# fanRegulator2.net
KiCad netlist of a schematic drawn in EAGLE
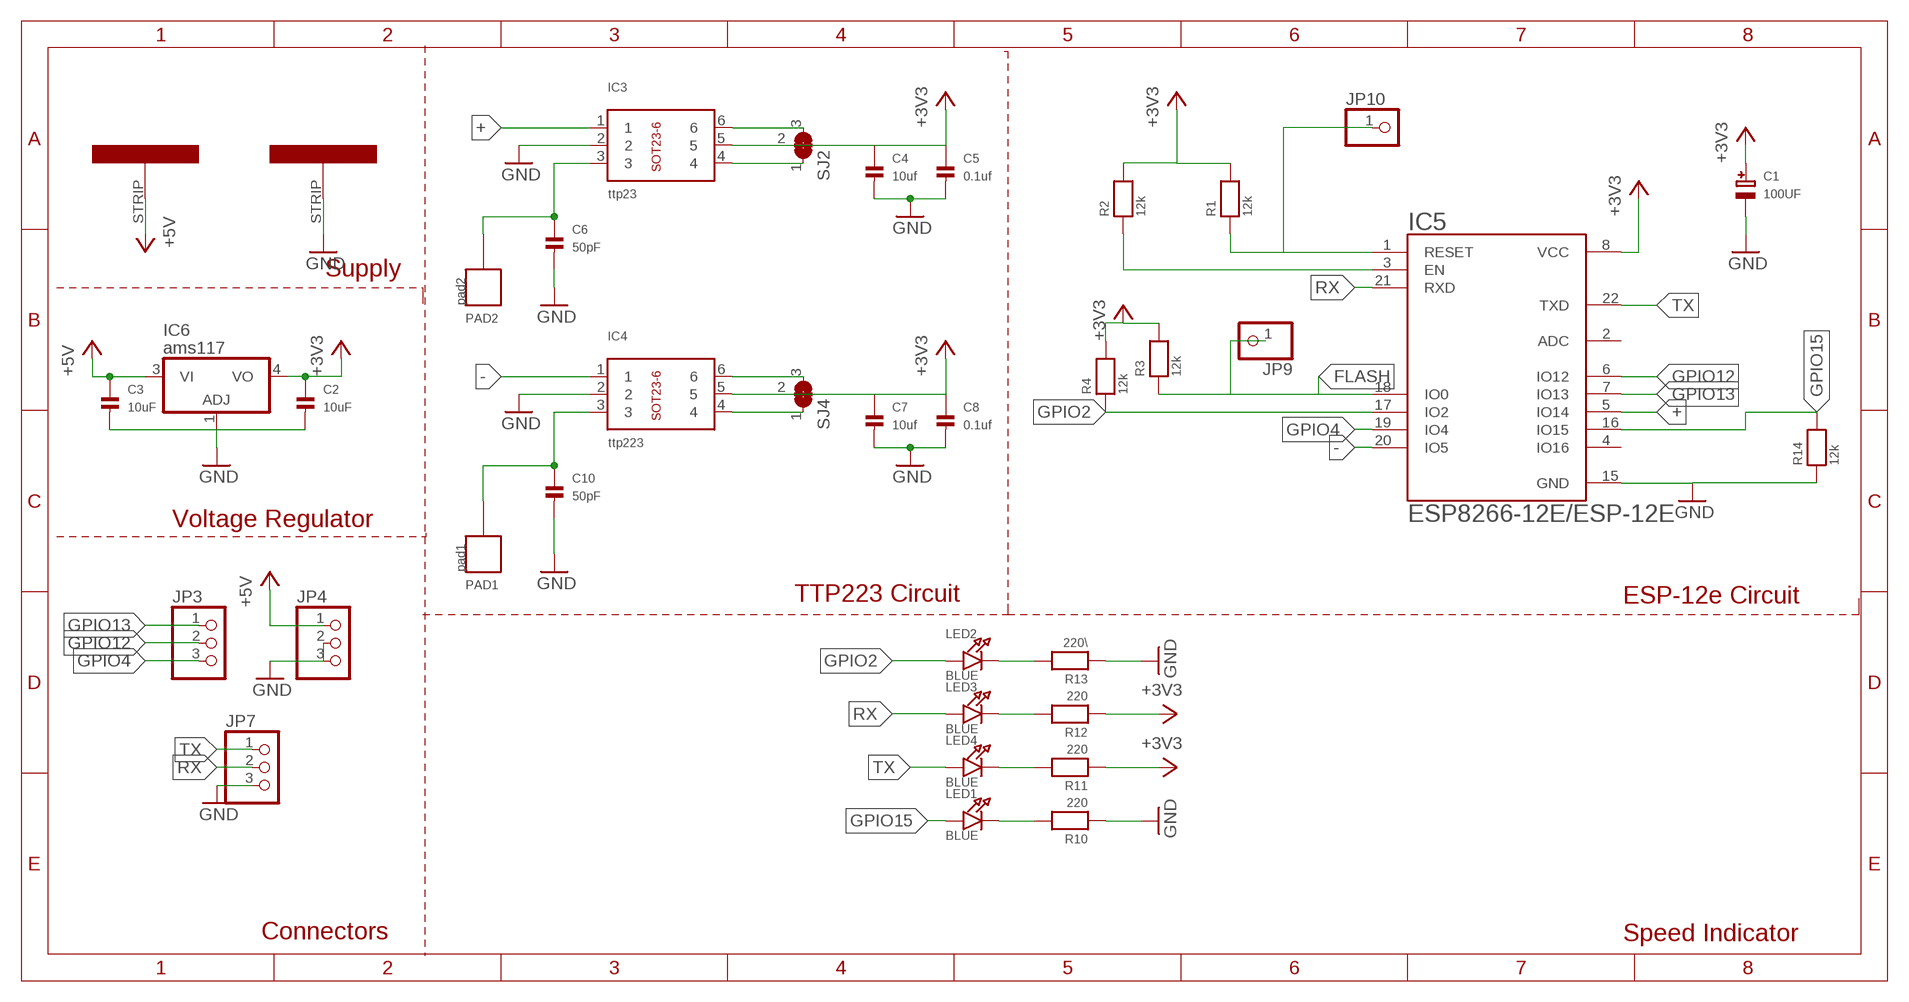
[diagram p0: schematic, sheet 1]
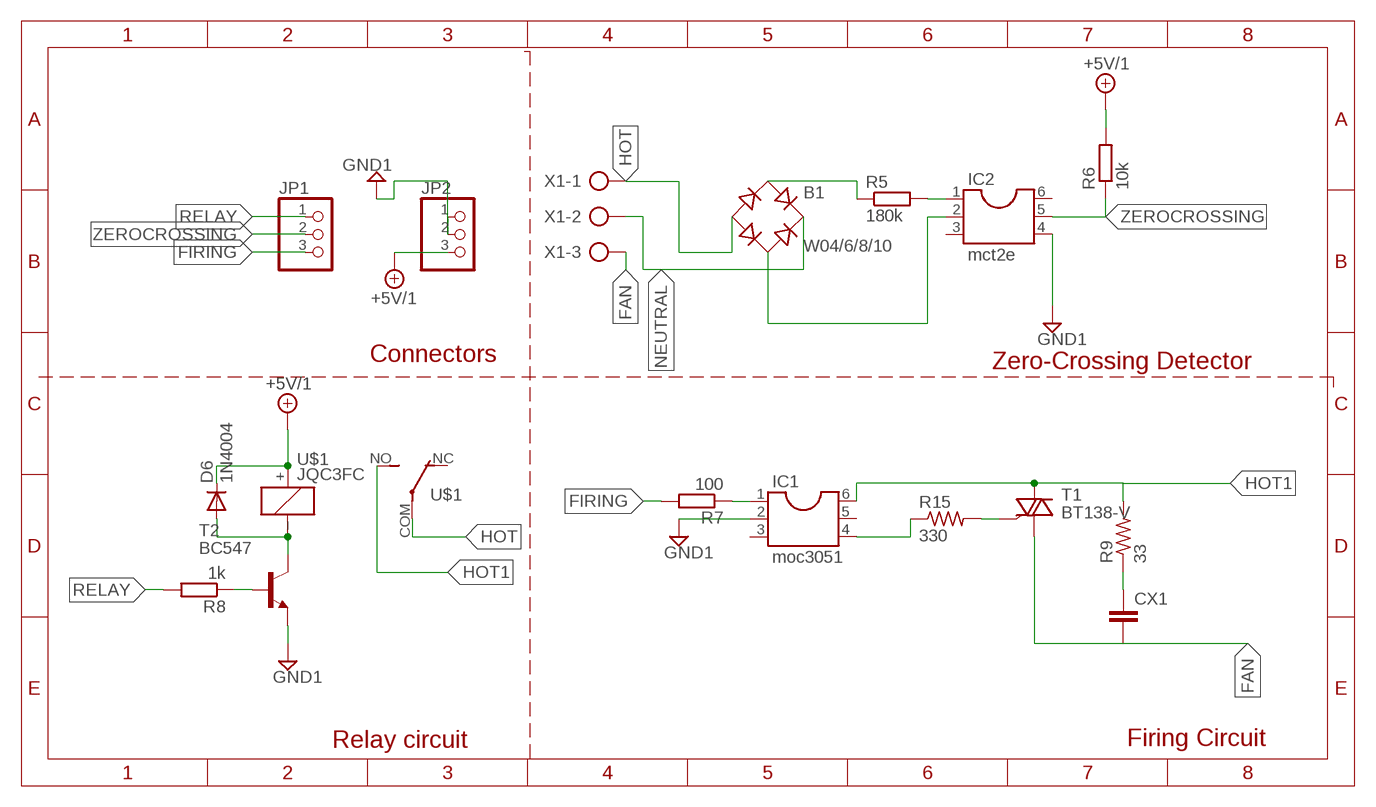
[diagram p1: schematic, sheet 2]

(export (version "E")
  (design (tool "Eeschema 10.0.6"))
  (components
    (comp (ref "C1")
      (value "100UF")
      (footprint "eagle-import:EIA6032-28_C-W")
      (libsource (lib "eagle-import") (part "CAP_TANTALUMC/6032_WAVE"))
    )
    (comp (ref "C2")
      (value "10uF")
      (footprint "eagle-import:0805")
      (libsource (lib "eagle-import") (part "CAP_CERAMIC0805"))
    )
    (comp (ref "C3")
      (value "10uF")
      (footprint "eagle-import:0805")
      (libsource (lib "eagle-import") (part "CAP_CERAMIC0805"))
    )
    (comp (ref "C4")
      (value "10uf")
      (footprint "eagle-import:0805")
      (libsource (lib "eagle-import") (part "CAP_CERAMIC0805"))
    )
    (comp (ref "C5")
      (value "0.1uf")
      (footprint "eagle-import:0805")
      (libsource (lib "eagle-import") (part "CAP_CERAMIC0805"))
    )
    (comp (ref "C6")
      (value "50pF")
      (footprint "eagle-import:0805")
      (libsource (lib "eagle-import") (part "CAP_CERAMIC0805"))
    )
    (comp (ref "C7")
      (value "10uf")
      (footprint "eagle-import:0805")
      (libsource (lib "eagle-import") (part "CAP_CERAMIC0805"))
    )
    (comp (ref "C8")
      (value "0.1uf")
      (footprint "eagle-import:0805")
      (libsource (lib "eagle-import") (part "CAP_CERAMIC0805"))
    )
    (comp (ref "C10")
      (value "50pF")
      (footprint "eagle-import:0805")
      (libsource (lib "eagle-import") (part "CAP_CERAMIC0805"))
    )
    (comp (ref "IC3")
      (value "ttp23")
      (footprint "eagle-import:BREAKOUT_SOT23-6")
      (libsource (lib "eagle-import") (part "BREAKOUT_SOT23-6"))
    )
    (comp (ref "IC4")
      (value "ttp223")
      (footprint "eagle-import:BREAKOUT_SOT23-6")
      (libsource (lib "eagle-import") (part "BREAKOUT_SOT23-6"))
    )
    (comp (ref "IC5")
      (value "ESP8266-12E/ESP-12E")
      (footprint "eagle-import:XCVR_ESP8266-12E_ESP-12E")
      (fields (field (name "MF") "AI-Thinker"))
      (libsource (lib "eagle-import") (part "ESP8266-12E/ESP-12E"))
    )
    (comp (ref "IC6")
      (value "ams117")
      (footprint "eagle-import:SOT223")
      (libsource (lib "eagle-import") (part "317EMP"))
    )
    (comp (ref "JP3")
      (value "PINHD-1X3")
      (footprint "eagle-import:1X03")
      (libsource (lib "eagle-import") (part "PINHD-1X3"))
    )
    (comp (ref "JP4")
      (value "PINHD-1X3")
      (footprint "eagle-import:1X03")
      (libsource (lib "eagle-import") (part "PINHD-1X3"))
    )
    (comp (ref "JP7")
      (value "PINHD-1X3CB")
      (footprint "eagle-import:1X03-CLEANBIG")
      (libsource (lib "eagle-import") (part "PINHD-1X3CB"))
    )
    (comp (ref "JP9")
      (value "PINHD-1X1")
      (footprint "eagle-import:1X01")
      (libsource (lib "eagle-import") (part "PINHD-1X1"))
    )
    (comp (ref "JP10")
      (value "PINHD-1X1")
      (footprint "eagle-import:1X01")
      (libsource (lib "eagle-import") (part "PINHD-1X1"))
    )
    (comp (ref "LED1")
      (value "BLUE")
      (footprint "eagle-import:CHIPLED_0805")
      (libsource (lib "eagle-import") (part "LED0805"))
    )
    (comp (ref "LED2")
      (value "BLUE")
      (footprint "eagle-import:CHIPLED_0805")
      (libsource (lib "eagle-import") (part "LED0805"))
    )
    (comp (ref "LED3")
      (value "BLUE")
      (footprint "eagle-import:CHIPLED_0805")
      (libsource (lib "eagle-import") (part "LED0805"))
    )
    (comp (ref "LED4")
      (value "BLUE")
      (footprint "eagle-import:CHIPLED_0805")
      (libsource (lib "eagle-import") (part "LED0805"))
    )
    (comp (ref "PAD1")
      (value "pad1")
      (footprint "eagle-import:CAP_TOUCHPAD")
      (libsource (lib "eagle-import") (part "CAP_TOUCHPAD"))
    )
    (comp (ref "PAD2")
      (value "pad2")
      (footprint "eagle-import:CAP_TOUCHPAD")
      (libsource (lib "eagle-import") (part "CAP_TOUCHPAD"))
    )
    (comp (ref "R1")
      (value "12k")
      (footprint "eagle-import:0805")
      (libsource (lib "eagle-import") (part "RESISTOR0805"))
    )
    (comp (ref "R2")
      (value "12k")
      (footprint "eagle-import:0805")
      (libsource (lib "eagle-import") (part "RESISTOR0805"))
    )
    (comp (ref "R3")
      (value "12k")
      (footprint "eagle-import:0805")
      (libsource (lib "eagle-import") (part "RESISTOR0805"))
    )
    (comp (ref "R4")
      (value "12k")
      (footprint "eagle-import:0805")
      (libsource (lib "eagle-import") (part "RESISTOR0805"))
    )
    (comp (ref "R10")
      (value "220")
      (footprint "eagle-import:0805")
      (libsource (lib "eagle-import") (part "RESISTOR0805"))
    )
    (comp (ref "R11")
      (value "220")
      (footprint "eagle-import:0805")
      (libsource (lib "eagle-import") (part "RESISTOR0805"))
    )
    (comp (ref "R12")
      (value "220")
      (footprint "eagle-import:0805")
      (libsource (lib "eagle-import") (part "RESISTOR0805"))
    )
    (comp (ref "R13")
      (value "220\\")
      (footprint "eagle-import:0805")
      (libsource (lib "eagle-import") (part "RESISTOR0805"))
    )
    (comp (ref "R14")
      (value "12k")
      (footprint "eagle-import:0805")
      (libsource (lib "eagle-import") (part "RESISTOR0805"))
    )
    (comp (ref "SJ2")
      (value "SOLDERJUMPER_2WAY0603")
      (footprint "eagle-import:SOLDERJUMPER_2WAY_OPEN_0603")
      (libsource (lib "eagle-import") (part "SOLDERJUMPER_2WAY0603"))
    )
    (comp (ref "SJ4")
      (value "SOLDERJUMPER_2WAY0603")
      (footprint "eagle-import:SOLDERJUMPER_2WAY_OPEN_0603")
      (libsource (lib "eagle-import") (part "SOLDERJUMPER_2WAY0603"))
    )
    (comp (ref "U$2")
      (value "STRIP")
      (footprint "eagle-import:STRIP")
      (libsource (lib "eagle-import") (part "STRIP"))
    )
    (comp (ref "U$3")
      (value "STRIP")
      (footprint "eagle-import:STRIP")
      (libsource (lib "eagle-import") (part "STRIP"))
    )
    (comp (ref "B1")
      (value "W04/6/8/10")
      (footprint "eagle-import:RB1A")
      (libsource (lib "eagle-import") (part "RB1A"))
    )
    (comp (ref "CX1")
      (value "C-EU050-024X044")
      (footprint "eagle-import:C050-024X044")
      (libsource (lib "eagle-import") (part "C-EU050-024X044"))
    )
    (comp (ref "D6")
      (value "1N4004")
      (footprint "eagle-import:DO41-10")
      (libsource (lib "eagle-import") (part "1N4004"))
    )
    (comp (ref "IC1")
      (value "moc3051")
      (footprint "eagle-import:DIL06")
      (libsource (lib "eagle-import") (part "DIL6"))
    )
    (comp (ref "IC2")
      (value "mct2e")
      (footprint "eagle-import:DIL06")
      (libsource (lib "eagle-import") (part "DIL6"))
    )
    (comp (ref "JP1")
      (value "PINHD-1X3")
      (footprint "eagle-import:1X03")
      (libsource (lib "eagle-import") (part "PINHD-1X3"))
    )
    (comp (ref "JP2")
      (value "PINHD-1X3")
      (footprint "eagle-import:1X03")
      (libsource (lib "eagle-import") (part "PINHD-1X3"))
    )
    (comp (ref "R5")
      (value "180k")
      (footprint "eagle-import:0309V")
      (libsource (lib "eagle-import") (part "R-EU_0309/V"))
    )
    (comp (ref "R6")
      (value "10k")
      (footprint "eagle-import:0204V")
      (libsource (lib "eagle-import") (part "R-EU_0204/2V"))
    )
    (comp (ref "R7")
      (value "100")
      (footprint "eagle-import:0204V")
      (libsource (lib "eagle-import") (part "R-EU_0204/2V"))
    )
    (comp (ref "R8")
      (value "1k")
      (footprint "eagle-import:0204V")
      (libsource (lib "eagle-import") (part "R-EU_0204/2V"))
    )
    (comp (ref "R9")
      (value "33")
      (footprint "eagle-import:0411V")
      (libsource (lib "eagle-import") (part "R-US_0411/3V"))
    )
    (comp (ref "R15")
      (value "330")
      (footprint "eagle-import:0207_2V")
      (libsource (lib "eagle-import") (part "R-US_0207/2V"))
    )
    (comp (ref "T1")
      (value "BT138-V")
      (footprint "eagle-import:TO220BV")
      (libsource (lib "eagle-import") (part "BT138-V"))
    )
    (comp (ref "T2")
      (value "BC547")
      (footprint "eagle-import:TO92")
      (libsource (lib "eagle-import") (part "BC547"))
    )
    (comp (ref "U$1")
      (value "JQC3FC")
      (footprint "eagle-import:JQC3FC")
      (libsource (lib "eagle-import") (part "JQC3FC"))
    )
    (comp (ref "X1")
      (value "AK500/3-H")
      (footprint "eagle-import:AK500_3-H")
      (libsource (lib "eagle-import") (part "AK500/3-H"))
    )
  )
  (nets
    (net (code "1") (name "+") (class "Default")
      (node (ref "IC3") (pin "1") (pinfunction "1_1") (pintype "bidirectional"))
      (node (ref "IC5") (pin "5") (pinfunction "IO14_5") (pintype "bidirectional"))
    )
    (net (code "2") (name "+3V3") (class "Default")
      (node (ref "C1") (pin "+") (pinfunction "+_+") (pintype "passive"))
      (node (ref "C2") (pin "1") (pinfunction "P$1_1") (pintype "passive"))
      (node (ref "C4") (pin "1") (pinfunction "P$1_1") (pintype "passive"))
      (node (ref "C5") (pin "1") (pinfunction "P$1_1") (pintype "passive"))
      (node (ref "C7") (pin "1") (pinfunction "P$1_1") (pintype "passive"))
      (node (ref "C8") (pin "1") (pinfunction "P$1_1") (pintype "passive"))
      (node (ref "IC3") (pin "5") (pinfunction "5_5") (pintype "bidirectional"))
      (node (ref "IC4") (pin "5") (pinfunction "5_5") (pintype "bidirectional"))
      (node (ref "IC5") (pin "8") (pinfunction "VCC_8") (pintype "power_in"))
      (node (ref "IC6") (pin "4") (pinfunction "VO_4") (pintype "passive"))
      (node (ref "R1") (pin "2") (pinfunction "2_2") (pintype "passive"))
      (node (ref "R11") (pin "1") (pinfunction "1_1") (pintype "passive"))
      (node (ref "R12") (pin "1") (pinfunction "1_1") (pintype "passive"))
      (node (ref "R2") (pin "2") (pinfunction "2_2") (pintype "passive"))
      (node (ref "R3") (pin "2") (pinfunction "2_2") (pintype "passive"))
      (node (ref "R4") (pin "2") (pinfunction "2_2") (pintype "passive"))
      (node (ref "SJ2") (pin "2") (pinfunction "2_2") (pintype "passive"))
      (node (ref "SJ4") (pin "2") (pinfunction "2_2") (pintype "passive"))
    )
    (net (code "3") (name "+5V") (class "Default")
      (node (ref "C3") (pin "1") (pinfunction "P$1_1") (pintype "passive"))
      (node (ref "IC6") (pin "3") (pinfunction "VI_3") (pintype "input"))
      (node (ref "JP4") (pin "1") (pinfunction "1_1") (pintype "passive"))
      (node (ref "U$2") (pin "STRIP") (pinfunction "STRIP_STRIP") (pintype "bidirectional"))
    )
    (net (code "4") (name "+5V{slash}1") (class "Default")
      (node (ref "D6") (pin "C") (pinfunction "C_C") (pintype "passive"))
      (node (ref "JP2") (pin "3") (pinfunction "3_3") (pintype "passive"))
      (node (ref "R6") (pin "2") (pinfunction "2_2") (pintype "passive"))
      (node (ref "U$1") (pin "+") (pinfunction "+_+") (pintype "passive"))
    )
    (net (code "5") (name "-") (class "Default")
      (node (ref "IC4") (pin "1") (pinfunction "1_1") (pintype "bidirectional"))
      (node (ref "IC5") (pin "20") (pinfunction "IO5_20") (pintype "bidirectional"))
    )
    (net (code "6") (name "FAN") (class "Default")
      (node (ref "CX1") (pin "2") (pinfunction "2_2") (pintype "passive"))
      (node (ref "T1") (pin "T1") (pinfunction "A1_T1") (pintype "passive"))
      (node (ref "X1") (pin "3") (pinfunction "KL_3") (pintype "passive"))
    )
    (net (code "7") (name "FIRING") (class "Default")
      (node (ref "JP1") (pin "3") (pinfunction "3_3") (pintype "passive"))
      (node (ref "R7") (pin "2") (pinfunction "2_2") (pintype "passive"))
    )
    (net (code "8") (name "FLASH") (class "Default")
      (node (ref "IC5") (pin "18") (pinfunction "IO0_18") (pintype "bidirectional"))
      (node (ref "JP9") (pin "1") (pinfunction "1_1") (pintype "passive"))
      (node (ref "R3") (pin "1") (pinfunction "1_1") (pintype "passive"))
    )
    (net (code "9") (name "GND") (class "Default")
      (node (ref "C1") (pin "-") (pinfunction "-_-") (pintype "passive"))
      (node (ref "C10") (pin "2") (pinfunction "P$2_2") (pintype "passive"))
      (node (ref "C2") (pin "2") (pinfunction "P$2_2") (pintype "passive"))
      (node (ref "C3") (pin "2") (pinfunction "P$2_2") (pintype "passive"))
      (node (ref "C4") (pin "2") (pinfunction "P$2_2") (pintype "passive"))
      (node (ref "C5") (pin "2") (pinfunction "P$2_2") (pintype "passive"))
      (node (ref "C6") (pin "2") (pinfunction "P$2_2") (pintype "passive"))
      (node (ref "C7") (pin "2") (pinfunction "P$2_2") (pintype "passive"))
      (node (ref "C8") (pin "2") (pinfunction "P$2_2") (pintype "passive"))
      (node (ref "IC3") (pin "2") (pinfunction "2_2") (pintype "bidirectional"))
      (node (ref "IC4") (pin "2") (pinfunction "2_2") (pintype "bidirectional"))
      (node (ref "IC5") (pin "15") (pinfunction "GND_15") (pintype "power_in"))
      (node (ref "IC6") (pin "1") (pinfunction "ADJ_1") (pintype "input"))
      (node (ref "JP4") (pin "2") (pinfunction "2_2") (pintype "passive"))
      (node (ref "JP4") (pin "3") (pinfunction "3_3") (pintype "passive"))
      (node (ref "JP7") (pin "3") (pinfunction "3_3") (pintype "passive"))
      (node (ref "R10") (pin "1") (pinfunction "1_1") (pintype "passive"))
      (node (ref "R13") (pin "1") (pinfunction "1_1") (pintype "passive"))
      (node (ref "R14") (pin "1") (pinfunction "1_1") (pintype "passive"))
      (node (ref "U$3") (pin "STRIP") (pinfunction "STRIP_STRIP") (pintype "bidirectional"))
    )
    (net (code "10") (name "GND1") (class "Default")
      (node (ref "IC1") (pin "2") (pinfunction "2_2") (pintype "passive"))
      (node (ref "IC2") (pin "4") (pinfunction "4_4") (pintype "passive"))
      (node (ref "JP2") (pin "1") (pinfunction "1_1") (pintype "passive"))
      (node (ref "JP2") (pin "2") (pinfunction "2_2") (pintype "passive"))
      (node (ref "T2") (pin "1") (pinfunction "E_1") (pintype "passive"))
    )
    (net (code "11") (name "GPIO2") (class "Default")
      (node (ref "IC5") (pin "17") (pinfunction "IO2_17") (pintype "bidirectional"))
      (node (ref "LED2") (pin "A") (pinfunction "A_A") (pintype "passive"))
      (node (ref "R4") (pin "1") (pinfunction "1_1") (pintype "passive"))
    )
    (net (code "12") (name "GPIO4") (class "Default")
      (node (ref "IC5") (pin "19") (pinfunction "IO4_19") (pintype "bidirectional"))
      (node (ref "JP3") (pin "3") (pinfunction "3_3") (pintype "passive"))
    )
    (net (code "13") (name "GPIO12") (class "Default")
      (node (ref "IC5") (pin "6") (pinfunction "IO12_6") (pintype "bidirectional"))
      (node (ref "JP3") (pin "2") (pinfunction "2_2") (pintype "passive"))
    )
    (net (code "14") (name "GPIO13") (class "Default")
      (node (ref "IC5") (pin "7") (pinfunction "IO13_7") (pintype "bidirectional"))
      (node (ref "JP3") (pin "1") (pinfunction "1_1") (pintype "passive"))
    )
    (net (code "15") (name "GPIO15") (class "Default")
      (node (ref "IC5") (pin "16") (pinfunction "IO15_16") (pintype "bidirectional"))
      (node (ref "LED1") (pin "A") (pinfunction "A_A") (pintype "passive"))
      (node (ref "R14") (pin "2") (pinfunction "2_2") (pintype "passive"))
    )
    (net (code "16") (name "HOT") (class "Default")
      (node (ref "B1") (pin "-") (pinfunction "-_-") (pintype "passive"))
      (node (ref "U$1") (pin "COM") (pinfunction "COM_COM") (pintype "passive"))
      (node (ref "X1") (pin "1") (pinfunction "KL_1") (pintype "passive"))
    )
    (net (code "17") (name "HOT1") (class "Default")
      (node (ref "IC1") (pin "6") (pinfunction "6_6") (pintype "passive"))
      (node (ref "R9") (pin "2") (pinfunction "2_2") (pintype "passive"))
      (node (ref "T1") (pin "T2") (pinfunction "A2_T2") (pintype "passive"))
      (node (ref "U$1") (pin "NO") (pinfunction "NO_NO") (pintype "passive"))
    )
    (net (code "18") (name "NEUTRAL") (class "Default")
      (node (ref "B1") (pin "+") (pinfunction "+_+") (pintype "passive"))
      (node (ref "X1") (pin "2") (pinfunction "KL_2") (pintype "passive"))
    )
    (net (code "19") (name "Net-(B1-PadAC1)") (class "Default")
      (node (ref "B1") (pin "AC1") (pinfunction "AC1_AC1") (pintype "passive"))
      (node (ref "R5") (pin "1") (pinfunction "1_1") (pintype "passive"))
    )
    (net (code "20") (name "Net-(B1-PadAC2)") (class "Default")
      (node (ref "B1") (pin "AC2") (pinfunction "AC2_AC2") (pintype "passive"))
      (node (ref "IC2") (pin "2") (pinfunction "2_2") (pintype "passive"))
    )
    (net (code "21") (name "Net-(C6-P$1)") (class "Default")
      (node (ref "C6") (pin "1") (pinfunction "P$1_1") (pintype "passive"))
      (node (ref "IC3") (pin "3") (pinfunction "3_3") (pintype "bidirectional"))
      (node (ref "PAD2") (pin "P$1") (pinfunction "P$1_P$1") (pintype "bidirectional"))
    )
    (net (code "22") (name "Net-(C10-P$1)") (class "Default")
      (node (ref "C10") (pin "1") (pinfunction "P$1_1") (pintype "passive"))
      (node (ref "IC4") (pin "3") (pinfunction "3_3") (pintype "bidirectional"))
      (node (ref "PAD1") (pin "P$1") (pinfunction "P$1_P$1") (pintype "bidirectional"))
    )
    (net (code "23") (name "Net-(CX1-Pad1)") (class "Default")
      (node (ref "CX1") (pin "1") (pinfunction "1_1") (pintype "passive"))
      (node (ref "R9") (pin "1") (pinfunction "1_1") (pintype "passive"))
    )
    (net (code "24") (name "Net-(IC1-Pad1)") (class "Default")
      (node (ref "IC1") (pin "1") (pinfunction "1_1") (pintype "passive"))
      (node (ref "R7") (pin "1") (pinfunction "1_1") (pintype "passive"))
    )
    (net (code "25") (name "Net-(IC1-Pad4)") (class "Default")
      (node (ref "IC1") (pin "4") (pinfunction "4_4") (pintype "passive"))
      (node (ref "R15") (pin "1") (pinfunction "1_1") (pintype "passive"))
    )
    (net (code "26") (name "Net-(IC2-Pad1)") (class "Default")
      (node (ref "IC2") (pin "1") (pinfunction "1_1") (pintype "passive"))
      (node (ref "R5") (pin "2") (pinfunction "2_2") (pintype "passive"))
    )
    (net (code "27") (name "Net-(IC3-Pad4)") (class "Default")
      (node (ref "IC3") (pin "4") (pinfunction "4_4") (pintype "bidirectional"))
      (node (ref "SJ2") (pin "1") (pinfunction "1_1") (pintype "passive"))
    )
    (net (code "28") (name "Net-(IC3-Pad6)") (class "Default")
      (node (ref "IC3") (pin "6") (pinfunction "6_6") (pintype "bidirectional"))
      (node (ref "SJ2") (pin "3") (pinfunction "3_3") (pintype "passive"))
    )
    (net (code "29") (name "Net-(IC4-Pad4)") (class "Default")
      (node (ref "IC4") (pin "4") (pinfunction "4_4") (pintype "bidirectional"))
      (node (ref "SJ4") (pin "1") (pinfunction "1_1") (pintype "passive"))
    )
    (net (code "30") (name "Net-(IC4-Pad6)") (class "Default")
      (node (ref "IC4") (pin "6") (pinfunction "6_6") (pintype "bidirectional"))
      (node (ref "SJ4") (pin "3") (pinfunction "3_3") (pintype "passive"))
    )
    (net (code "31") (name "Net-(IC5-EN)") (class "Default")
      (node (ref "IC5") (pin "3") (pinfunction "EN_3") (pintype "input"))
      (node (ref "R2") (pin "1") (pinfunction "1_1") (pintype "passive"))
    )
    (net (code "32") (name "Net-(IC5-RESET)") (class "Default")
      (node (ref "IC5") (pin "1") (pinfunction "RESET_1") (pintype "input"))
      (node (ref "JP10") (pin "1") (pinfunction "1_1") (pintype "passive"))
      (node (ref "R1") (pin "1") (pinfunction "1_1") (pintype "passive"))
    )
    (net (code "33") (name "Net-(LED1-PadC)") (class "Default")
      (node (ref "LED1") (pin "C") (pinfunction "C_C") (pintype "passive"))
      (node (ref "R10") (pin "2") (pinfunction "2_2") (pintype "passive"))
    )
    (net (code "34") (name "Net-(LED2-PadC)") (class "Default")
      (node (ref "LED2") (pin "C") (pinfunction "C_C") (pintype "passive"))
      (node (ref "R13") (pin "2") (pinfunction "2_2") (pintype "passive"))
    )
    (net (code "35") (name "Net-(LED3-PadC)") (class "Default")
      (node (ref "LED3") (pin "C") (pinfunction "C_C") (pintype "passive"))
      (node (ref "R12") (pin "2") (pinfunction "2_2") (pintype "passive"))
    )
    (net (code "36") (name "Net-(LED4-PadC)") (class "Default")
      (node (ref "LED4") (pin "C") (pinfunction "C_C") (pintype "passive"))
      (node (ref "R11") (pin "2") (pinfunction "2_2") (pintype "passive"))
    )
    (net (code "37") (name "Net-(R15-Pad2)") (class "Default")
      (node (ref "R15") (pin "2") (pinfunction "2_2") (pintype "passive"))
      (node (ref "T1") (pin "G") (pinfunction "G_G") (pintype "passive"))
    )
    (net (code "38") (name "Net-(T2-B)") (class "Default")
      (node (ref "R8") (pin "1") (pinfunction "1_1") (pintype "passive"))
      (node (ref "T2") (pin "2") (pinfunction "B_2") (pintype "passive"))
    )
    (net (code "39") (name "Net-(T2-C)") (class "Default")
      (node (ref "D6") (pin "A") (pinfunction "A_A") (pintype "passive"))
      (node (ref "T2") (pin "3") (pinfunction "C_3") (pintype "passive"))
      (node (ref "U$1") (pin "_") (pinfunction "-__") (pintype "passive"))
    )
    (net (code "40") (name "RELAY") (class "Default")
      (node (ref "JP1") (pin "1") (pinfunction "1_1") (pintype "passive"))
      (node (ref "R8") (pin "2") (pinfunction "2_2") (pintype "passive"))
    )
    (net (code "41") (name "RX") (class "Default")
      (node (ref "IC5") (pin "21") (pinfunction "RXD_21") (pintype "input"))
      (node (ref "JP7") (pin "2") (pinfunction "2_2") (pintype "passive"))
      (node (ref "LED3") (pin "A") (pinfunction "A_A") (pintype "passive"))
    )
    (net (code "42") (name "TX") (class "Default")
      (node (ref "IC5") (pin "22") (pinfunction "TXD_22") (pintype "output"))
      (node (ref "JP7") (pin "1") (pinfunction "1_1") (pintype "passive"))
      (node (ref "LED4") (pin "A") (pinfunction "A_A") (pintype "passive"))
    )
    (net (code "43") (name "ZEROCROSSING") (class "Default")
      (node (ref "IC2") (pin "5") (pinfunction "5_5") (pintype "passive"))
      (node (ref "JP1") (pin "2") (pinfunction "2_2") (pintype "passive"))
      (node (ref "R6") (pin "1") (pinfunction "1_1") (pintype "passive"))
    )
    (net (code "44") (name "unconnected-(IC1-Pad3)") (class "Default")
      (node (ref "IC1") (pin "3") (pinfunction "3_3") (pintype "passive"))
    )
    (net (code "45") (name "unconnected-(IC1-Pad5)") (class "Default")
      (node (ref "IC1") (pin "5") (pinfunction "5_5") (pintype "passive"))
    )
    (net (code "46") (name "unconnected-(IC2-Pad3)") (class "Default")
      (node (ref "IC2") (pin "3") (pinfunction "3_3") (pintype "passive"))
    )
    (net (code "47") (name "unconnected-(IC2-Pad6)") (class "Default")
      (node (ref "IC2") (pin "6") (pinfunction "6_6") (pintype "passive"))
    )
    (net (code "48") (name "unconnected-(IC5-ADC-Pad2)") (class "Default")
      (node (ref "IC5") (pin "2") (pinfunction "ADC_2") (pintype "passive"))
    )
    (net (code "49") (name "unconnected-(IC5-IO16-Pad4)") (class "Default")
      (node (ref "IC5") (pin "4") (pinfunction "IO16_4") (pintype "bidirectional"))
    )
    (net (code "50") (name "unconnected-(U$1-PadNC)") (class "Default")
      (node (ref "U$1") (pin "NC") (pinfunction "NC_NC") (pintype "passive"))
    )
  )
)
